# PWM_CAN_SD.net
KiCad netlist of a schematic drawn in Altium Designer
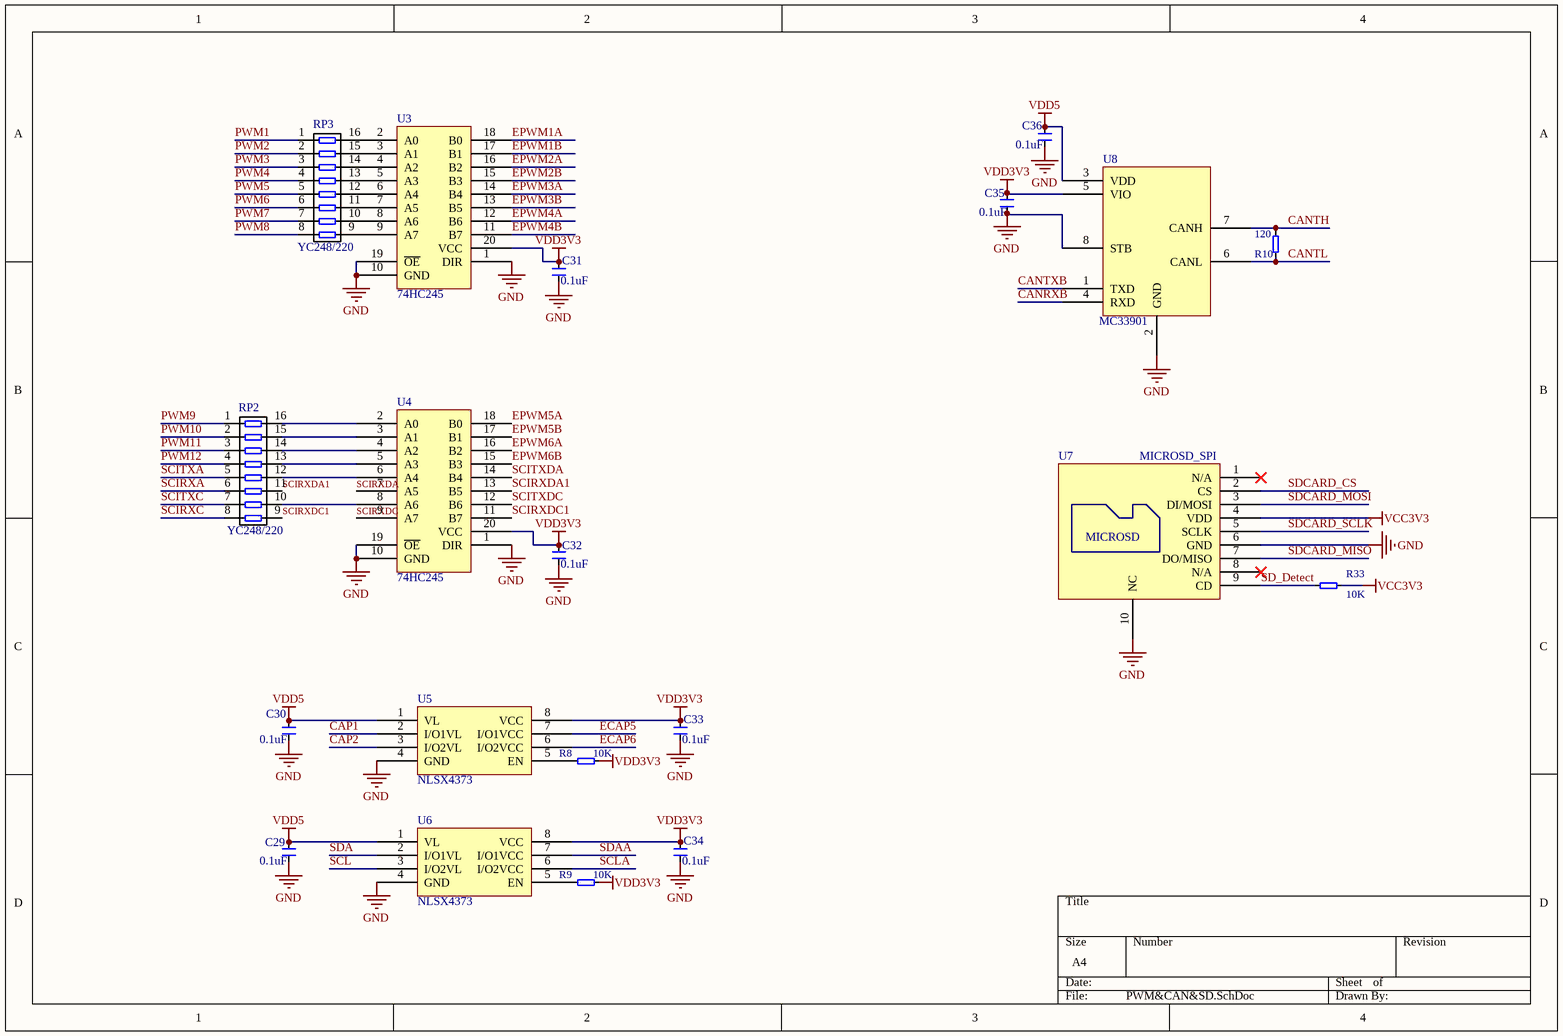
[diagram p0: PWM&CAN&SD.SchDoc]

(export (version "E")
  (design (tool "Eeschema 10.0.6"))
  (components
    (comp (ref "C29") (value "0.1uF") (footprint "0603C") (libsource (lib "研发中心原理图库文件") (part "C")))
    (comp (ref "C30") (value "0.1uF") (footprint "0603C") (libsource (lib "研发中心原理图库文件") (part "C")))
    (comp (ref "C31") (value "0.1uF") (footprint "0603C") (libsource (lib "研发中心原理图库文件") (part "C")))
    (comp (ref "C32") (value "0.1uF") (footprint "0603C") (libsource (lib "研发中心原理图库文件") (part "C")))
    (comp (ref "C33") (value "0.1uF") (footprint "0603C") (libsource (lib "研发中心原理图库文件") (part "C")))
    (comp (ref "C34") (value "0.1uF") (footprint "0603C") (libsource (lib "研发中心原理图库文件") (part "C")))
    (comp (ref "C35") (value "0.1uF") (footprint "0603C") (libsource (lib "研发中心原理图库文件") (part "C")))
    (comp (ref "C36") (value "0.1uF") (footprint "0603C") (libsource (lib "研发中心原理图库文件") (part "C")))
    (comp (ref "R8") (value "10K") (footprint "0603R") (libsource (lib "研发中心原理图库文件") (part "R")))
    (comp (ref "R9") (value "10K") (footprint "0603R") (libsource (lib "研发中心原理图库文件") (part "R")))
    (comp (ref "R10") (value "120") (footprint "0603R") (libsource (lib "研发中心原理图库文件") (part "R")))
    (comp (ref "R33") (value "10K") (footprint "0603R") (libsource (lib "研发中心原理图库文件") (part "R")))
    (comp (ref "RP2")
      (value "YC248/220")
      (footprint "YC248(0603x8)")
      (libsource (lib "研发中心原理图库文件") (part "RP"))
    )
    (comp (ref "RP3")
      (value "YC248/220")
      (footprint "研发中心PCB库文件:YC248(0603x8)")
      (libsource (lib "研发中心原理图库文件") (part "RP"))
    )
    (comp (ref "U3") (value "74HC245") (footprint "TSSOP20") (libsource (lib "研发中心原理图库文件") (part "74HC245")))
    (comp (ref "U4") (value "74HC245") (footprint "TSSOP20") (libsource (lib "研发中心原理图库文件") (part "74HC245")))
    (comp (ref "U5") (value "NLSX4373") (footprint "UDFN8") (libsource (lib "研发中心原理图库文件") (part "NLSX4373")))
    (comp (ref "U6") (value "NLSX4373") (footprint "UDFN8") (libsource (lib "研发中心原理图库文件") (part "NLSX4373")))
    (comp (ref "U7")
      (value "MICROSD_SPI")
      (footprint "研发中心PCB库文件:microsd")
      (libsource (lib "研发中心原理图库文件") (part "MICROSD_SPI"))
    )
    (comp (ref "U8") (value "MC33901") (footprint "SOIC-8") (libsource (lib "研发中心原理图库文件") (part "MC33901")))
  )
  (nets
    (net (code "1") (name "/CANRXB") (class "Default")
      (node (ref "U8") (pin "4") (pinfunction "RXD_4") (pintype "passive"))
    )
    (net (code "2") (name "/CANTH") (class "Default")
      (node (ref "R10") (pin "1") (pintype "passive"))
      (node (ref "U8") (pin "7") (pinfunction "CANH_7") (pintype "passive"))
    )
    (net (code "3") (name "/CANTL") (class "Default")
      (node (ref "R10") (pin "2") (pintype "passive"))
      (node (ref "U8") (pin "6") (pinfunction "CANL_6") (pintype "passive"))
    )
    (net (code "4") (name "/CANTXB") (class "Default")
      (node (ref "U8") (pin "1") (pinfunction "TXD_1") (pintype "passive"))
    )
    (net (code "5") (name "/CAP1") (class "Default")
      (node (ref "U5") (pin "2") (pinfunction "I/O1VL_2") (pintype "passive"))
    )
    (net (code "6") (name "/CAP2") (class "Default")
      (node (ref "U5") (pin "3") (pinfunction "I/O2VL_3") (pintype "passive"))
    )
    (net (code "7") (name "/ECAP5") (class "Default")
      (node (ref "U5") (pin "7") (pinfunction "I/O1VCC_7") (pintype "passive"))
    )
    (net (code "8") (name "/ECAP6") (class "Default")
      (node (ref "U5") (pin "6") (pinfunction "I/O2VCC_6") (pintype "passive"))
    )
    (net (code "9") (name "/EPWM1A") (class "Default")
      (node (ref "U3") (pin "18") (pinfunction "B0_18") (pintype "passive"))
    )
    (net (code "10") (name "/EPWM1B") (class "Default")
      (node (ref "U3") (pin "17") (pinfunction "B1_17") (pintype "passive"))
    )
    (net (code "11") (name "/EPWM2A") (class "Default")
      (node (ref "U3") (pin "16") (pinfunction "B2_16") (pintype "passive"))
    )
    (net (code "12") (name "/EPWM2B") (class "Default")
      (node (ref "U3") (pin "15") (pinfunction "B3_15") (pintype "passive"))
    )
    (net (code "13") (name "/EPWM3A") (class "Default")
      (node (ref "U3") (pin "14") (pinfunction "B4_14") (pintype "passive"))
    )
    (net (code "14") (name "/EPWM3B") (class "Default")
      (node (ref "U3") (pin "13") (pinfunction "B5_13") (pintype "passive"))
    )
    (net (code "15") (name "/EPWM4A") (class "Default")
      (node (ref "U3") (pin "12") (pinfunction "B6_12") (pintype "passive"))
    )
    (net (code "16") (name "/EPWM4B") (class "Default")
      (node (ref "U3") (pin "11") (pinfunction "B7_11") (pintype "passive"))
    )
    (net (code "17") (name "/EPWM5A") (class "Default")
      (node (ref "U4") (pin "18") (pinfunction "B0_18") (pintype "passive"))
    )
    (net (code "18") (name "/EPWM5B") (class "Default")
      (node (ref "U4") (pin "17") (pinfunction "B1_17") (pintype "passive"))
    )
    (net (code "19") (name "/EPWM6A") (class "Default")
      (node (ref "U4") (pin "16") (pinfunction "B2_16") (pintype "passive"))
    )
    (net (code "20") (name "/EPWM6B") (class "Default")
      (node (ref "U4") (pin "15") (pinfunction "B3_15") (pintype "passive"))
    )
    (net (code "21") (name "/PWM1") (class "Default")
      (node (ref "RP3") (pin "1") (pinfunction "1_1") (pintype "passive"))
    )
    (net (code "22") (name "/PWM2") (class "Default")
      (node (ref "RP3") (pin "2") (pinfunction "2_2") (pintype "passive"))
    )
    (net (code "23") (name "/PWM3") (class "Default")
      (node (ref "RP3") (pin "3") (pinfunction "3_3") (pintype "passive"))
    )
    (net (code "24") (name "/PWM4") (class "Default")
      (node (ref "RP3") (pin "4") (pinfunction "4_4") (pintype "passive"))
    )
    (net (code "25") (name "/PWM5") (class "Default")
      (node (ref "RP3") (pin "5") (pinfunction "5_5") (pintype "passive"))
    )
    (net (code "26") (name "/PWM6") (class "Default")
      (node (ref "RP3") (pin "6") (pinfunction "6_6") (pintype "passive"))
    )
    (net (code "27") (name "/PWM7") (class "Default")
      (node (ref "RP3") (pin "7") (pinfunction "7_7") (pintype "passive"))
    )
    (net (code "28") (name "/PWM8") (class "Default")
      (node (ref "RP3") (pin "8") (pinfunction "8_8") (pintype "passive"))
    )
    (net (code "29") (name "/PWM9") (class "Default")
      (node (ref "RP2") (pin "1") (pinfunction "1_1") (pintype "passive"))
    )
    (net (code "30") (name "/PWM10") (class "Default")
      (node (ref "RP2") (pin "2") (pinfunction "2_2") (pintype "passive"))
    )
    (net (code "31") (name "/PWM11") (class "Default")
      (node (ref "RP2") (pin "3") (pinfunction "3_3") (pintype "passive"))
    )
    (net (code "32") (name "/PWM12") (class "Default")
      (node (ref "RP2") (pin "4") (pinfunction "4_4") (pintype "passive"))
    )
    (net (code "33") (name "/SCIRXA") (class "Default")
      (node (ref "RP2") (pin "6") (pinfunction "6_6") (pintype "passive"))
    )
    (net (code "34") (name "/SCIRXC") (class "Default")
      (node (ref "RP2") (pin "8") (pinfunction "8_8") (pintype "passive"))
    )
    (net (code "35") (name "/SCIRXDA") (class "Default")
      (node (ref "U4") (pin "7") (pinfunction "A5_7") (pintype "passive"))
    )
    (net (code "36") (name "/SCIRXDA1") (class "Default")
      (node (ref "RP2") (pin "11") (pinfunction "11_11") (pintype "passive"))
      (node (ref "U4") (pin "13") (pinfunction "B5_13") (pintype "passive"))
    )
    (net (code "37") (name "/SCIRXDC") (class "Default")
      (node (ref "U4") (pin "9") (pinfunction "A7_9") (pintype "passive"))
    )
    (net (code "38") (name "/SCIRXDC1") (class "Default")
      (node (ref "RP2") (pin "9") (pinfunction "9_9") (pintype "passive"))
      (node (ref "U4") (pin "11") (pinfunction "B7_11") (pintype "passive"))
    )
    (net (code "39") (name "/SCITXA") (class "Default")
      (node (ref "RP2") (pin "5") (pinfunction "5_5") (pintype "passive"))
    )
    (net (code "40") (name "/SCITXC") (class "Default")
      (node (ref "RP2") (pin "7") (pinfunction "7_7") (pintype "passive"))
    )
    (net (code "41") (name "/SCITXDA") (class "Default")
      (node (ref "U4") (pin "14") (pinfunction "B4_14") (pintype "passive"))
    )
    (net (code "42") (name "/SCITXDC") (class "Default")
      (node (ref "U4") (pin "12") (pinfunction "B6_12") (pintype "passive"))
    )
    (net (code "43") (name "/SCL") (class "Default")
      (node (ref "U6") (pin "3") (pinfunction "I/O2VL_3") (pintype "passive"))
    )
    (net (code "44") (name "/SCLA") (class "Default")
      (node (ref "U6") (pin "6") (pinfunction "I/O2VCC_6") (pintype "passive"))
    )
    (net (code "45") (name "/SDA") (class "Default")
      (node (ref "U6") (pin "2") (pinfunction "I/O1VL_2") (pintype "passive"))
    )
    (net (code "46") (name "/SDAA") (class "Default")
      (node (ref "U6") (pin "7") (pinfunction "I/O1VCC_7") (pintype "passive"))
    )
    (net (code "47") (name "/SDCARD_CS") (class "Default")
      (node (ref "U7") (pin "2") (pinfunction "CS_2") (pintype "passive"))
    )
    (net (code "48") (name "/SDCARD_MISO") (class "Default")
      (node (ref "U7") (pin "7") (pinfunction "DO/MISO_7") (pintype "passive"))
    )
    (net (code "49") (name "/SDCARD_MOSI") (class "Default")
      (node (ref "U7") (pin "3") (pinfunction "DI/MOSI_3") (pintype "passive"))
    )
    (net (code "50") (name "/SDCARD_SCLK") (class "Default")
      (node (ref "U7") (pin "5") (pinfunction "SCLK_5") (pintype "passive"))
    )
    (net (code "51") (name "/SD_Detect") (class "Default")
      (node (ref "R33") (pin "2") (pintype "passive"))
      (node (ref "U7") (pin "9") (pinfunction "CD_9") (pintype "passive"))
    )
    (net (code "52") (name "GND") (class "Default")
      (node (ref "C29") (pin "1") (pintype "passive"))
      (node (ref "C30") (pin "1") (pintype "passive"))
      (node (ref "C31") (pin "1") (pintype "passive"))
      (node (ref "C32") (pin "1") (pintype "passive"))
      (node (ref "C33") (pin "1") (pintype "passive"))
      (node (ref "C34") (pin "1") (pintype "passive"))
      (node (ref "C35") (pin "1") (pintype "passive"))
      (node (ref "C36") (pin "1") (pintype "passive"))
      (node (ref "U3") (pin "1") (pinfunction "DIR_1") (pintype "passive"))
      (node (ref "U3") (pin "10") (pinfunction "GND_10") (pintype "passive"))
      (node (ref "U3") (pin "19") (pinfunction "~{OE}_19") (pintype "passive"))
      (node (ref "U4") (pin "1") (pinfunction "DIR_1") (pintype "passive"))
      (node (ref "U4") (pin "10") (pinfunction "GND_10") (pintype "passive"))
      (node (ref "U4") (pin "19") (pinfunction "~{OE}_19") (pintype "passive"))
      (node (ref "U5") (pin "4") (pinfunction "GND_4") (pintype "passive"))
      (node (ref "U6") (pin "4") (pinfunction "GND_4") (pintype "passive"))
      (node (ref "U7") (pin "10") (pinfunction "NC_10") (pintype "passive"))
      (node (ref "U7") (pin "6") (pinfunction "GND_6") (pintype "passive"))
      (node (ref "U8") (pin "2") (pinfunction "GND_2") (pintype "passive"))
      (node (ref "U8") (pin "8") (pinfunction "STB_8") (pintype "passive"))
    )
    (net (code "53") (name "Net-(U3-A0)") (class "Default")
      (node (ref "RP3") (pin "16") (pinfunction "16_16") (pintype "passive"))
      (node (ref "U3") (pin "2") (pinfunction "A0_2") (pintype "passive"))
    )
    (net (code "54") (name "Net-(U3-A1)") (class "Default")
      (node (ref "RP3") (pin "15") (pinfunction "15_15") (pintype "passive"))
      (node (ref "U3") (pin "3") (pinfunction "A1_3") (pintype "passive"))
    )
    (net (code "55") (name "Net-(U3-A2)") (class "Default")
      (node (ref "RP3") (pin "14") (pinfunction "14_14") (pintype "passive"))
      (node (ref "U3") (pin "4") (pinfunction "A2_4") (pintype "passive"))
    )
    (net (code "56") (name "Net-(U3-A3)") (class "Default")
      (node (ref "RP3") (pin "13") (pinfunction "13_13") (pintype "passive"))
      (node (ref "U3") (pin "5") (pinfunction "A3_5") (pintype "passive"))
    )
    (net (code "57") (name "Net-(U3-A4)") (class "Default")
      (node (ref "RP3") (pin "12") (pinfunction "12_12") (pintype "passive"))
      (node (ref "U3") (pin "6") (pinfunction "A4_6") (pintype "passive"))
    )
    (net (code "58") (name "Net-(U3-A5)") (class "Default")
      (node (ref "RP3") (pin "11") (pinfunction "11_11") (pintype "passive"))
      (node (ref "U3") (pin "7") (pinfunction "A5_7") (pintype "passive"))
    )
    (net (code "59") (name "Net-(U3-A6)") (class "Default")
      (node (ref "RP3") (pin "10") (pinfunction "10_10") (pintype "passive"))
      (node (ref "U3") (pin "8") (pinfunction "A6_8") (pintype "passive"))
    )
    (net (code "60") (name "Net-(U3-A7)") (class "Default")
      (node (ref "RP3") (pin "9") (pinfunction "9_9") (pintype "passive"))
      (node (ref "U3") (pin "9") (pinfunction "A7_9") (pintype "passive"))
    )
    (net (code "61") (name "Net-(U4-A0)") (class "Default")
      (node (ref "RP2") (pin "16") (pinfunction "16_16") (pintype "passive"))
      (node (ref "U4") (pin "2") (pinfunction "A0_2") (pintype "passive"))
    )
    (net (code "62") (name "Net-(U4-A1)") (class "Default")
      (node (ref "RP2") (pin "15") (pinfunction "15_15") (pintype "passive"))
      (node (ref "U4") (pin "3") (pinfunction "A1_3") (pintype "passive"))
    )
    (net (code "63") (name "Net-(U4-A2)") (class "Default")
      (node (ref "RP2") (pin "14") (pinfunction "14_14") (pintype "passive"))
      (node (ref "U4") (pin "4") (pinfunction "A2_4") (pintype "passive"))
    )
    (net (code "64") (name "Net-(U4-A3)") (class "Default")
      (node (ref "RP2") (pin "13") (pinfunction "13_13") (pintype "passive"))
      (node (ref "U4") (pin "5") (pinfunction "A3_5") (pintype "passive"))
    )
    (net (code "65") (name "Net-(U4-A4)") (class "Default")
      (node (ref "RP2") (pin "12") (pinfunction "12_12") (pintype "passive"))
      (node (ref "U4") (pin "6") (pinfunction "A4_6") (pintype "passive"))
    )
    (net (code "66") (name "Net-(U4-A6)") (class "Default")
      (node (ref "RP2") (pin "10") (pinfunction "10_10") (pintype "passive"))
      (node (ref "U4") (pin "8") (pinfunction "A6_8") (pintype "passive"))
    )
    (net (code "67") (name "Net-(U5-EN)") (class "Default")
      (node (ref "R8") (pin "1") (pintype "passive"))
      (node (ref "U5") (pin "5") (pinfunction "EN_5") (pintype "passive"))
    )
    (net (code "68") (name "Net-(U6-EN)") (class "Default")
      (node (ref "R9") (pin "1") (pintype "passive"))
      (node (ref "U6") (pin "5") (pinfunction "EN_5") (pintype "passive"))
    )
    (net (code "69") (name "VCC3V3") (class "Default")
      (node (ref "R33") (pin "1") (pintype "passive"))
      (node (ref "U7") (pin "4") (pinfunction "VDD_4") (pintype "passive"))
    )
    (net (code "70") (name "VDD3V3") (class "Default")
      (node (ref "C31") (pin "2") (pintype "passive"))
      (node (ref "C32") (pin "2") (pintype "passive"))
      (node (ref "C33") (pin "2") (pintype "passive"))
      (node (ref "C34") (pin "2") (pintype "passive"))
      (node (ref "C35") (pin "2") (pintype "passive"))
      (node (ref "R8") (pin "2") (pintype "passive"))
      (node (ref "R9") (pin "2") (pintype "passive"))
      (node (ref "U3") (pin "20") (pinfunction "VCC_20") (pintype "passive"))
      (node (ref "U4") (pin "20") (pinfunction "VCC_20") (pintype "passive"))
      (node (ref "U5") (pin "8") (pinfunction "VCC_8") (pintype "passive"))
      (node (ref "U6") (pin "8") (pinfunction "VCC_8") (pintype "passive"))
      (node (ref "U8") (pin "5") (pinfunction "VIO_5") (pintype "passive"))
    )
    (net (code "71") (name "VDD5") (class "Default")
      (node (ref "C29") (pin "2") (pintype "passive"))
      (node (ref "C30") (pin "2") (pintype "passive"))
      (node (ref "C36") (pin "2") (pintype "passive"))
      (node (ref "U5") (pin "1") (pinfunction "VL_1") (pintype "passive"))
      (node (ref "U6") (pin "1") (pinfunction "VL_1") (pintype "passive"))
      (node (ref "U8") (pin "3") (pinfunction "VDD_3") (pintype "passive"))
    )
    (net (code "72") (name "unconnected-(U7-N{slash}A-Pad1)") (class "Default")
      (node (ref "U7") (pin "1") (pinfunction "N/A_1") (pintype "passive+no_connect"))
    )
    (net (code "73") (name "unconnected-(U7-N{slash}A-Pad8)") (class "Default")
      (node (ref "U7") (pin "8") (pinfunction "N/A_8") (pintype "passive+no_connect"))
    )
  )
)
